# D4_2020-10-05_17-04-56.net
KiCad netlist of a schematic drawn in EasyEDA
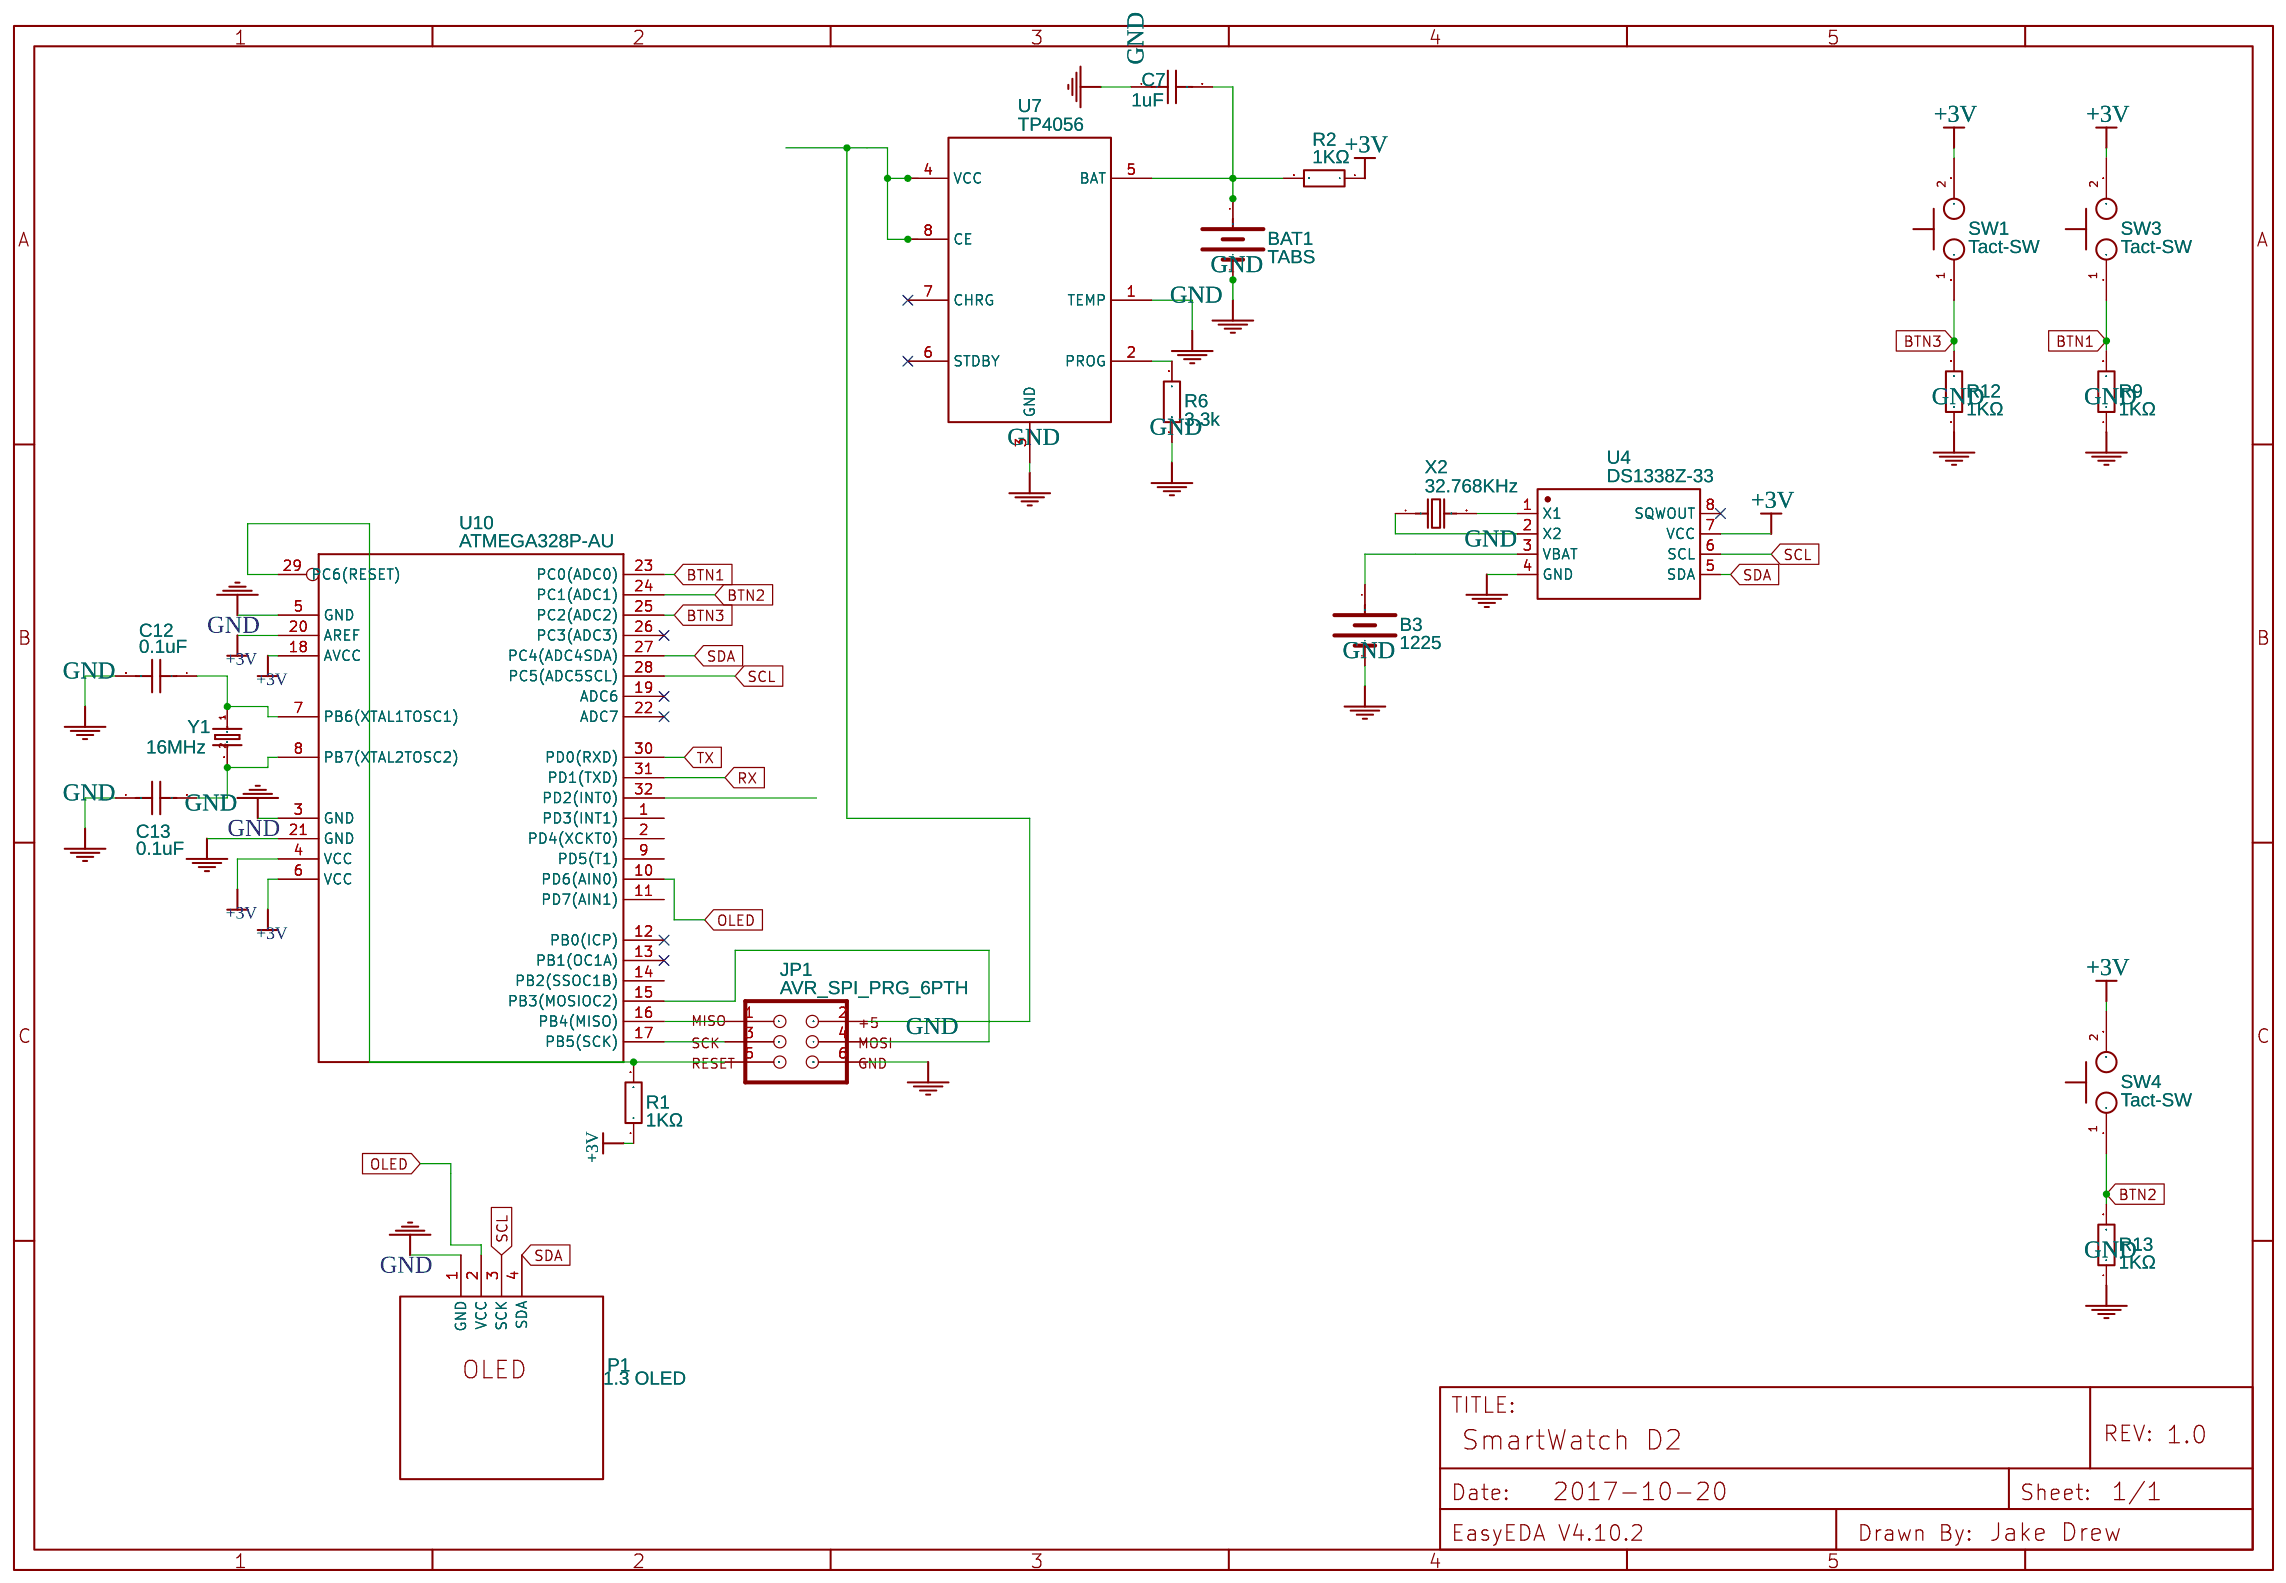
[diagram p0: schematic sheet]

(export (version "E")
  (design (tool "Eeschema 10.0.6"))
  (components
    (comp (ref "B3")
      (value "1225")
      (fields (field (name "BOM_Manufacturer Part") "?"))
      (libsource (lib "") (part "Unknown_665_295"))
    )
    (comp (ref "BAT1")
      (value "TABS")
      (fields (field (name "BOM_Manufacturer Part") "?"))
      (libsource (lib "") (part "Unknown_600_105"))
    )
    (comp (ref "C7")
      (value "1uF")
      (fields
        (field (name "BOM_Manufacturer Part") "0805B105K250NT")
        (field (name "BOM_Supplier Part") "C89190")
      )
      (libsource (lib "") (part "Unknown_570_30"))
    )
    (comp (ref "C12")
      (value "0.1uF")
      (fields
        (field (name "BOM_Manufacturer Part") "0805B105K250NT")
        (field (name "BOM_Supplier Part") "C89190")
      )
      (libsource (lib "") (part "Unknown_70_320"))
    )
    (comp (ref "C13")
      (value "0.1uF")
      (fields
        (field (name "BOM_Manufacturer Part") "0805B105K250NT")
        (field (name "BOM_Supplier Part") "C89190")
      )
      (libsource (lib "") (part "Unknown_70_380"))
    )
    (comp (ref "JP1")
      (value "AVR_SPI_PRG_6PTH")
      (fields (field (name "BOM_Manufacturer Part") "?"))
      (libsource (lib "") (part "Unknown_380_500"))
    )
    (comp (ref "P1")
      (value "1.3 OLED")
      (fields (field (name "BOM_Manufacturer Part") "?"))
      (libsource (lib "") (part "Unknown_270_715"))
    )
    (comp (ref "R1")
      (value "1KΩ")
      (fields
        (field (name "BOM_Manufacturer Part") "1206W4F1001T5E")
        (field (name "BOM_Supplier Part") "C4410")
      )
      (libsource (lib "") (part "Unknown_305_530"))
    )
    (comp (ref "R2")
      (value "1KΩ")
      (fields
        (field (name "BOM_Manufacturer Part") "1206W4F1001T5E")
        (field (name "BOM_Supplier Part") "C4410")
      )
      (libsource (lib "") (part "Unknown_645_75"))
    )
    (comp (ref "R6")
      (value "3.3k")
      (fields
        (field (name "BOM_Manufacturer Part") "1210W3F680KT5E")
        (field (name "BOM_Supplier Part") "C38887")
      )
      (libsource (lib "") (part "Unknown_570_185"))
    )
    (comp (ref "R9")
      (value "1KΩ")
      (fields
        (field (name "BOM_Manufacturer Part") "1206W4F1001T5E")
        (field (name "BOM_Supplier Part") "C4410")
      )
      (libsource (lib "") (part "Unknown_1030_180"))
    )
    (comp (ref "R12")
      (value "1KΩ")
      (fields
        (field (name "BOM_Manufacturer Part") "1206W4F1001T5E")
        (field (name "BOM_Supplier Part") "C4410")
      )
      (libsource (lib "") (part "Unknown_955_180"))
    )
    (comp (ref "R13")
      (value "1KΩ")
      (fields
        (field (name "BOM_Manufacturer Part") "1206W4F1001T5E")
        (field (name "BOM_Supplier Part") "C4410")
      )
      (libsource (lib "") (part "Unknown_1030_600"))
    )
    (comp (ref "SW1")
      (value "Tact-SW")
      (fields (field (name "BOM_Manufacturer Part") "TL3330AF260QG"))
      (libsource (lib "") (part "Unknown_955_100"))
    )
    (comp (ref "SW3")
      (value "Tact-SW")
      (fields (field (name "BOM_Manufacturer Part") "TL3330AF260QG"))
      (libsource (lib "") (part "Unknown_1030_100"))
    )
    (comp (ref "SW4")
      (value "Tact-SW")
      (fields (field (name "BOM_Manufacturer Part") "TL3330AF260QG"))
      (libsource (lib "") (part "Unknown_1030_520"))
    )
    (comp (ref "U4")
      (value "DS1338Z-33")
      (fields (field (name "BOM_Supplier Part") "C49105"))
      (libsource (lib "") (part "Unknown_790_230"))
    )
    (comp (ref "U7")
      (value "TP4056")
      (fields (field (name "BOM_Supplier Part") "C16581"))
      (libsource (lib "") (part "Unknown_500_135"))
    )
    (comp (ref "U10") (value "ATMEGA328P-AU") (libsource (lib "") (part "Unknown_225_385")))
    (comp (ref "X2")
      (value "32.768KHz")
      (fields
        (field (name "BOM_Manufacturer Part") "DT-38 32.768KHz")
        (field (name "BOM_Supplier Part") "C93228")
      )
      (libsource (lib "") (part "Unknown_700_240"))
    )
    (comp (ref "Y1")
      (value "16MHz")
      (fields (field (name "BOM_Manufacturer Part") "X053201602002"))
      (libsource (lib "") (part "Unknown_105_350"))
    )
  )
  (nets
    (net (code "1") (name "+3V") (class "Default")
      (node (ref "R1") (pin "1") (pinfunction "1_1") (pintype "input"))
      (node (ref "R2") (pin "1") (pinfunction "1_1") (pintype "input"))
      (node (ref "SW1") (pin "2") (pinfunction "2_2") (pintype "unspecified"))
      (node (ref "SW3") (pin "2") (pinfunction "2_2") (pintype "unspecified"))
      (node (ref "SW4") (pin "2") (pinfunction "2_2") (pintype "unspecified"))
      (node (ref "U10") (pin "18") (pinfunction "AVCC_18") (pintype "unspecified"))
      (node (ref "U10") (pin "20") (pinfunction "AREF_20") (pintype "unspecified"))
      (node (ref "U10") (pin "4") (pinfunction "VCC_4") (pintype "unspecified"))
      (node (ref "U10") (pin "6") (pinfunction "VCC_6") (pintype "unspecified"))
      (node (ref "U4") (pin "7") (pinfunction "VCC_7") (pintype "unspecified"))
    )
    (net (code "2") (name "BTN1") (class "Default")
      (node (ref "R9") (pin "2") (pinfunction "2_2") (pintype "input"))
      (node (ref "SW3") (pin "1") (pinfunction "1_1") (pintype "unspecified"))
      (node (ref "U10") (pin "23") (pinfunction "PC0(ADC0)_23") (pintype "unspecified"))
    )
    (net (code "3") (name "BTN2") (class "Default")
      (node (ref "R13") (pin "2") (pinfunction "2_2") (pintype "input"))
      (node (ref "SW4") (pin "1") (pinfunction "1_1") (pintype "unspecified"))
      (node (ref "U10") (pin "24") (pinfunction "PC1(ADC1)_24") (pintype "unspecified"))
    )
    (net (code "4") (name "BTN3") (class "Default")
      (node (ref "R12") (pin "2") (pinfunction "2_2") (pintype "input"))
      (node (ref "SW1") (pin "1") (pinfunction "1_1") (pintype "unspecified"))
      (node (ref "U10") (pin "25") (pinfunction "PC2(ADC2)_25") (pintype "unspecified"))
    )
    (net (code "5") (name "GND") (class "Default")
      (node (ref "B3") (pin "-") (pinfunction "-_-") (pintype "passive"))
      (node (ref "BAT1") (pin "-") (pinfunction "-_-") (pintype "passive"))
      (node (ref "C12") (pin "2") (pinfunction "2_2") (pintype "unspecified"))
      (node (ref "C13") (pin "1") (pinfunction "1_1") (pintype "unspecified"))
      (node (ref "C7") (pin "1") (pinfunction "1_1") (pintype "unspecified"))
      (node (ref "JP1") (pin "6") (pinfunction "6_6") (pintype "unspecified"))
      (node (ref "P1") (pin "1") (pinfunction "GND_1") (pintype "unspecified"))
      (node (ref "R12") (pin "1") (pinfunction "1_1") (pintype "input"))
      (node (ref "R13") (pin "1") (pinfunction "1_1") (pintype "input"))
      (node (ref "R6") (pin "1") (pinfunction "1_1") (pintype "input"))
      (node (ref "R9") (pin "1") (pinfunction "1_1") (pintype "input"))
      (node (ref "U10") (pin "21") (pinfunction "GND_21") (pintype "unspecified"))
      (node (ref "U10") (pin "3") (pinfunction "GND_3") (pintype "unspecified"))
      (node (ref "U10") (pin "5") (pinfunction "GND_5") (pintype "unspecified"))
      (node (ref "U4") (pin "4") (pinfunction "GND_4") (pintype "unspecified"))
      (node (ref "U7") (pin "1") (pinfunction "TEMP_1") (pintype "unspecified"))
      (node (ref "U7") (pin "3") (pinfunction "GND_3") (pintype "unspecified"))
    )
    (net (code "6") (name "Net-(U4-VBAT)") (class "Default")
      (node (ref "B3") (pin "+") (pinfunction "+_+") (pintype "passive"))
      (node (ref "U4") (pin "3") (pinfunction "VBAT_3") (pintype "unspecified"))
    )
    (net (code "7") (name "Net-(U4-X1)") (class "Default")
      (node (ref "U4") (pin "1") (pinfunction "X1_1") (pintype "unspecified"))
      (node (ref "X2") (pin "2") (pinfunction "2_2") (pintype "unspecified"))
    )
    (net (code "8") (name "Net-(U4-X2)") (class "Default")
      (node (ref "U4") (pin "2") (pinfunction "X2_2") (pintype "unspecified"))
      (node (ref "X2") (pin "1") (pinfunction "1_1") (pintype "unspecified"))
    )
    (net (code "9") (name "Net-(U7-BAT)") (class "Default")
      (node (ref "BAT1") (pin "+") (pinfunction "+_+") (pintype "passive"))
      (node (ref "C7") (pin "2") (pinfunction "2_2") (pintype "unspecified"))
      (node (ref "R2") (pin "2") (pinfunction "2_2") (pintype "input"))
      (node (ref "U7") (pin "5") (pinfunction "BAT_5") (pintype "unspecified"))
    )
    (net (code "10") (name "Net-(U7-CE)") (class "Default")
      (node (ref "JP1") (pin "2") (pinfunction "2_2") (pintype "unspecified"))
      (node (ref "U7") (pin "4") (pinfunction "VCC_4") (pintype "unspecified"))
      (node (ref "U7") (pin "8") (pinfunction "CE_8") (pintype "unspecified"))
    )
    (net (code "11") (name "Net-(U7-PROG)") (class "Default")
      (node (ref "R6") (pin "2") (pinfunction "2_2") (pintype "input"))
      (node (ref "U7") (pin "2") (pinfunction "PROG_2") (pintype "unspecified"))
    )
    (net (code "12") (name "Net-(U10-PB3(MOSIOC2))") (class "Default")
      (node (ref "JP1") (pin "4") (pinfunction "4_4") (pintype "unspecified"))
      (node (ref "U10") (pin "15") (pinfunction "PB3(MOSIOC2)_15") (pintype "unspecified"))
    )
    (net (code "13") (name "Net-(U10-PB4(MISO))") (class "Default")
      (node (ref "JP1") (pin "1") (pinfunction "1_1") (pintype "unspecified"))
      (node (ref "U10") (pin "16") (pinfunction "PB4(MISO)_16") (pintype "unspecified"))
    )
    (net (code "14") (name "Net-(U10-PB5(SCK))") (class "Default")
      (node (ref "JP1") (pin "3") (pinfunction "3_3") (pintype "unspecified"))
      (node (ref "U10") (pin "17") (pinfunction "PB5(SCK)_17") (pintype "unspecified"))
    )
    (net (code "15") (name "Net-(U10-PB6(XTAL1TOSC1))") (class "Default")
      (node (ref "C12") (pin "1") (pinfunction "1_1") (pintype "unspecified"))
      (node (ref "U10") (pin "7") (pinfunction "PB6(XTAL1TOSC1)_7") (pintype "unspecified"))
      (node (ref "Y1") (pin "1") (pinfunction "1_1") (pintype "unspecified"))
    )
    (net (code "16") (name "Net-(U10-PB7(XTAL2TOSC2))") (class "Default")
      (node (ref "C13") (pin "2") (pinfunction "2_2") (pintype "unspecified"))
      (node (ref "U10") (pin "8") (pinfunction "PB7(XTAL2TOSC2)_8") (pintype "unspecified"))
      (node (ref "Y1") (pin "2") (pinfunction "2_2") (pintype "unspecified"))
    )
    (net (code "17") (name "Net-(U10-PC6(RESET))") (class "Default")
      (node (ref "JP1") (pin "5") (pinfunction "5_5") (pintype "unspecified"))
      (node (ref "R1") (pin "2") (pinfunction "2_2") (pintype "input"))
      (node (ref "U10") (pin "29") (pinfunction "PC6(RESET)_29") (pintype "unspecified"))
    )
    (net (code "18") (name "OLED") (class "Default")
      (node (ref "P1") (pin "2") (pinfunction "VCC_2") (pintype "unspecified"))
      (node (ref "U10") (pin "10") (pinfunction "PD6(AIN0)_10") (pintype "unspecified"))
    )
    (net (code "19") (name "RX") (class "Default")
      (node (ref "U10") (pin "31") (pinfunction "PD1(TXD)_31") (pintype "unspecified"))
    )
    (net (code "20") (name "SCL") (class "Default")
      (node (ref "P1") (pin "3") (pinfunction "SCK_3") (pintype "unspecified"))
      (node (ref "U10") (pin "28") (pinfunction "PC5(ADC5SCL)_28") (pintype "unspecified"))
      (node (ref "U4") (pin "6") (pinfunction "SCL_6") (pintype "unspecified"))
    )
    (net (code "21") (name "SDA") (class "Default")
      (node (ref "P1") (pin "4") (pinfunction "SDA_4") (pintype "unspecified"))
      (node (ref "U10") (pin "27") (pinfunction "PC4(ADC4SDA)_27") (pintype "unspecified"))
      (node (ref "U4") (pin "5") (pinfunction "SDA_5") (pintype "unspecified"))
    )
    (net (code "22") (name "TX") (class "Default")
      (node (ref "U10") (pin "30") (pinfunction "PD0(RXD)_30") (pintype "unspecified"))
    )
    (net (code "23") (name "unconnected-(U4-SQWOUT-Pad8)") (class "Default")
      (node (ref "U4") (pin "8") (pinfunction "SQWOUT_8") (pintype "unspecified+no_connect"))
    )
    (net (code "24") (name "unconnected-(U7-CHRG-Pad7)") (class "Default")
      (node (ref "U7") (pin "7") (pinfunction "CHRG_7") (pintype "unspecified+no_connect"))
    )
    (net (code "25") (name "unconnected-(U7-STDBY-Pad6)") (class "Default")
      (node (ref "U7") (pin "6") (pinfunction "STDBY_6") (pintype "unspecified+no_connect"))
    )
    (net (code "26") (name "unconnected-(U10-ADC6-Pad19)") (class "Default")
      (node (ref "U10") (pin "19") (pinfunction "ADC6_19") (pintype "unspecified+no_connect"))
    )
    (net (code "27") (name "unconnected-(U10-ADC7-Pad22)") (class "Default")
      (node (ref "U10") (pin "22") (pinfunction "ADC7_22") (pintype "unspecified+no_connect"))
    )
    (net (code "28") (name "unconnected-(U10-PB0(ICP)-Pad12)") (class "Default")
      (node (ref "U10") (pin "12") (pinfunction "PB0(ICP)_12") (pintype "unspecified+no_connect"))
    )
    (net (code "29") (name "unconnected-(U10-PB1(OC1A)-Pad13)") (class "Default")
      (node (ref "U10") (pin "13") (pinfunction "PB1(OC1A)_13") (pintype "unspecified+no_connect"))
    )
    (net (code "30") (name "unconnected-(U10-PB2(SSOC1B)-Pad14)") (class "Default")
      (node (ref "U10") (pin "14") (pinfunction "PB2(SSOC1B)_14") (pintype "unspecified"))
    )
    (net (code "31") (name "unconnected-(U10-PC3(ADC3)-Pad26)") (class "Default")
      (node (ref "U10") (pin "26") (pinfunction "PC3(ADC3)_26") (pintype "unspecified+no_connect"))
    )
    (net (code "32") (name "unconnected-(U10-PD2(INT0)-Pad32)") (class "Default")
      (node (ref "U10") (pin "32") (pinfunction "PD2(INT0)_32") (pintype "unspecified"))
    )
    (net (code "33") (name "unconnected-(U10-PD3(INT1)-Pad1)") (class "Default")
      (node (ref "U10") (pin "1") (pinfunction "PD3(INT1)_1") (pintype "unspecified"))
    )
    (net (code "34") (name "unconnected-(U10-PD4(XCKT0)-Pad2)") (class "Default")
      (node (ref "U10") (pin "2") (pinfunction "PD4(XCKT0)_2") (pintype "unspecified"))
    )
    (net (code "35") (name "unconnected-(U10-PD5(T1)-Pad9)") (class "Default")
      (node (ref "U10") (pin "9") (pinfunction "PD5(T1)_9") (pintype "unspecified"))
    )
    (net (code "36") (name "unconnected-(U10-PD7(AIN1)-Pad11)") (class "Default")
      (node (ref "U10") (pin "11") (pinfunction "PD7(AIN1)_11") (pintype "unspecified"))
    )
  )
)
